# Power_Volume_PCB.net
KiCad netlist of a schematic drawn in EAGLE
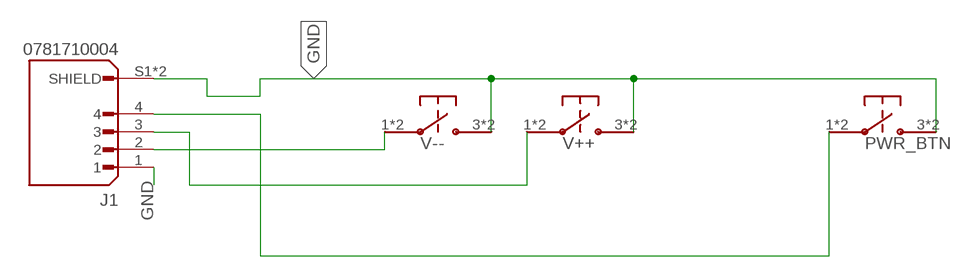
[diagram p0: schematic, sheet 1]

(export (version "E")
  (design (tool "Eeschema 10.0.6"))
  (components
    (comp (ref "J1")
      (value "0781710004")
      (footprint "eagle-import:MOLEX_0781710004")
      (fields (field (name "MF") "Molex"))
      (libsource (lib "eagle-import") (part "0781710004"))
    )
    (comp (ref "PWR_BTN")
      (value "TL3315NF100Q")
      (footprint "eagle-import:TL3315NF100Q")
      (fields (field (name "DIGI-KEY_PART_NUMBER") "EG4620CT-ND") (field (name "MF") "E-Switch"))
      (libsource (lib "eagle-import") (part "TL3315NF100Q"))
    )
    (comp (ref "V++")
      (value "TL3315NF100Q")
      (footprint "eagle-import:TL3315NF100Q")
      (fields (field (name "DIGI-KEY_PART_NUMBER") "EG4620CT-ND") (field (name "MF") "E-Switch"))
      (libsource (lib "eagle-import") (part "TL3315NF100Q"))
    )
    (comp (ref "V--")
      (value "TL3315NF100Q")
      (footprint "eagle-import:TL3315NF100Q")
      (fields (field (name "DIGI-KEY_PART_NUMBER") "EG4620CT-ND") (field (name "MF") "E-Switch"))
      (libsource (lib "eagle-import") (part "TL3315NF100Q"))
    )
  )
  (nets
    (net (code "1") (name "GND") (class "Default")
      (node (ref "J1") (pin "1") (pinfunction "1_1") (pintype "passive"))
      (node (ref "J1") (pin "S1") (pinfunction "SHIELD_S1") (pintype "passive"))
      (node (ref "J1") (pin "S2") (pinfunction "SHIELD_S2") (pintype "passive"))
      (node (ref "PWR_BTN") (pin "3") (pinfunction "P$2_3") (pintype "passive"))
      (node (ref "PWR_BTN") (pin "4") (pinfunction "P$2_4") (pintype "passive"))
      (node (ref "V++") (pin "3") (pinfunction "P$2_3") (pintype "passive"))
      (node (ref "V++") (pin "4") (pinfunction "P$2_4") (pintype "passive"))
      (node (ref "V--") (pin "3") (pinfunction "P$2_3") (pintype "passive"))
      (node (ref "V--") (pin "4") (pinfunction "P$2_4") (pintype "passive"))
    )
    (net (code "2") (name "Net-(J1-Pad2)") (class "Default")
      (node (ref "J1") (pin "2") (pinfunction "2_2") (pintype "passive"))
      (node (ref "V--") (pin "1") (pinfunction "P$1_1") (pintype "passive"))
      (node (ref "V--") (pin "2") (pinfunction "P$1_2") (pintype "passive"))
    )
    (net (code "3") (name "Net-(J1-Pad3)") (class "Default")
      (node (ref "J1") (pin "3") (pinfunction "3_3") (pintype "passive"))
      (node (ref "V++") (pin "1") (pinfunction "P$1_1") (pintype "passive"))
      (node (ref "V++") (pin "2") (pinfunction "P$1_2") (pintype "passive"))
    )
    (net (code "4") (name "Net-(J1-Pad4)") (class "Default")
      (node (ref "J1") (pin "4") (pinfunction "4_4") (pintype "passive"))
      (node (ref "PWR_BTN") (pin "1") (pinfunction "P$1_1") (pintype "passive"))
      (node (ref "PWR_BTN") (pin "2") (pinfunction "P$1_2") (pintype "passive"))
    )
  )
)
